# Power.net
KiCad netlist of a schematic drawn in Altium Designer
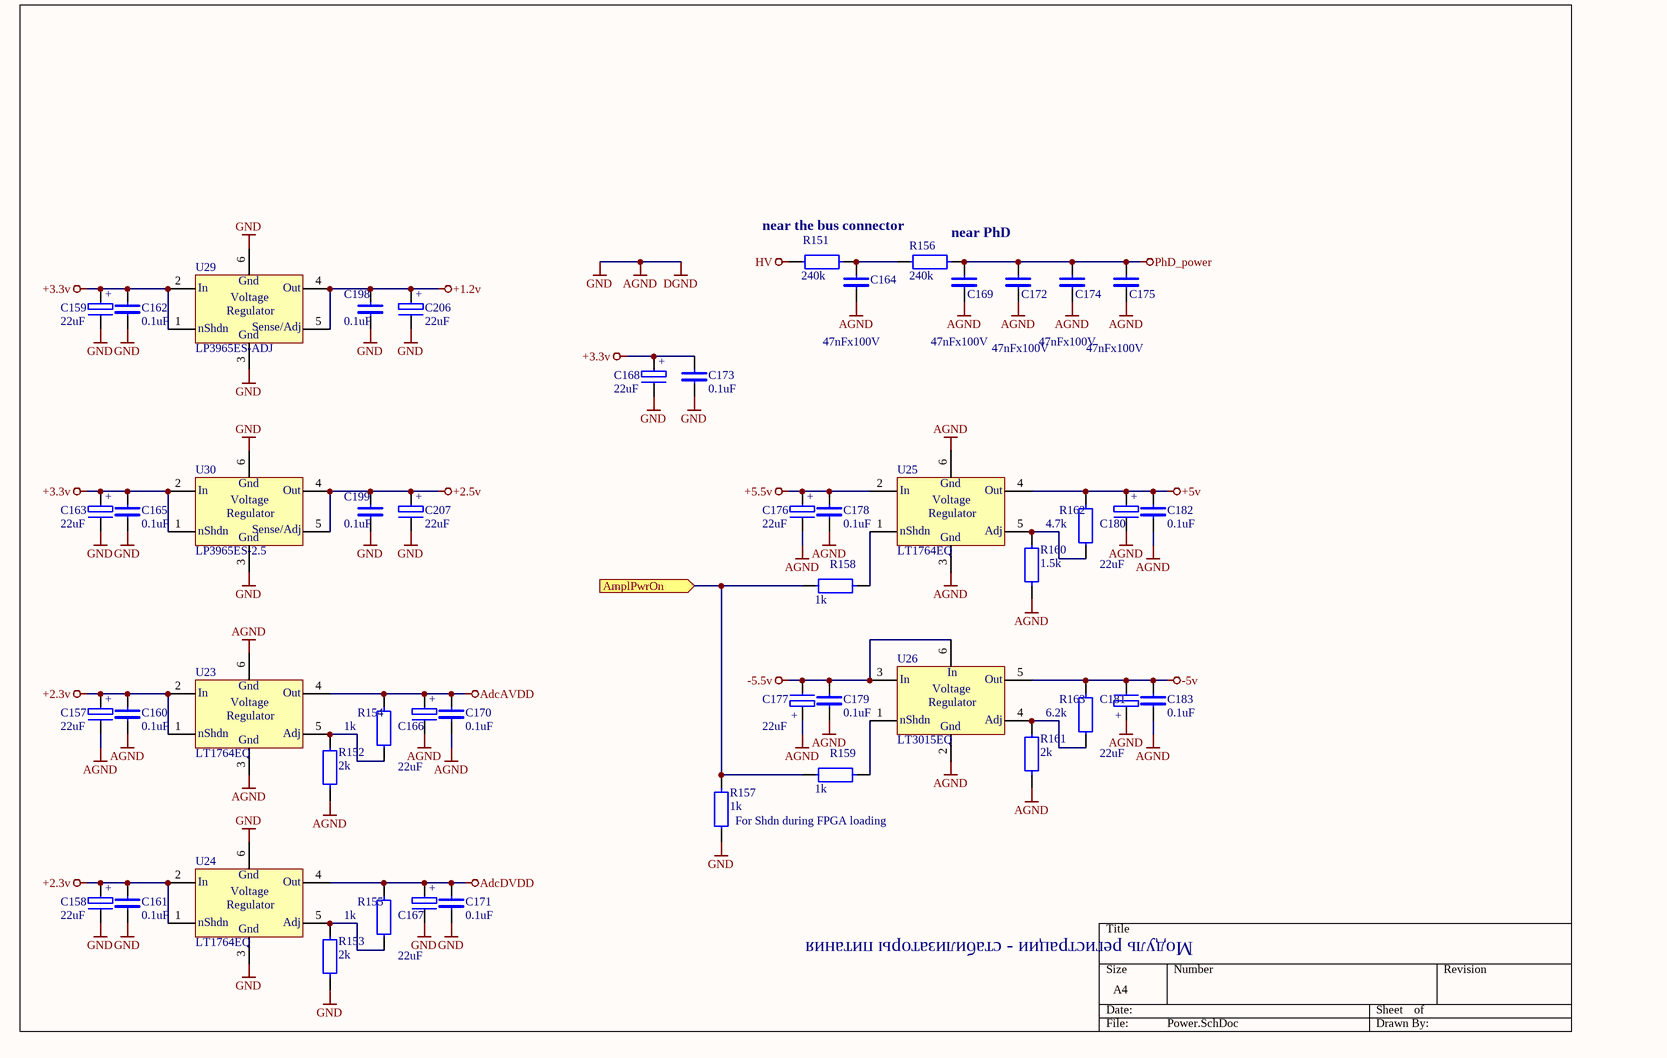
[diagram p0: Power.SchDoc]

(export (version "E")
  (design (tool "Eeschema 10.0.6"))
  (components
    (comp (ref "C157") (value "22uF") (footprint "CP6032") (libsource (lib "*") (part "C POL")))
    (comp (ref "C158") (value "22uF") (footprint "CP6032") (libsource (lib "*") (part "C POL")))
    (comp (ref "C159") (value "22uF") (footprint "CP6032") (libsource (lib "*") (part "C POL")))
    (comp (ref "C160") (value "0.1uF") (footprint "0603") (libsource (lib "*") (part "C")))
    (comp (ref "C161") (value "0.1uF") (footprint "0603") (libsource (lib "*") (part "C")))
    (comp (ref "C162") (value "0.1uF") (footprint "0603") (libsource (lib "*") (part "C")))
    (comp (ref "C163") (value "22uF") (footprint "CP6032") (libsource (lib "*") (part "C POL")))
    (comp (ref "C164") (value "47nFx100V") (footprint "1206") (libsource (lib "*") (part "C")))
    (comp (ref "C165") (value "0.1uF") (footprint "0603") (libsource (lib "*") (part "C")))
    (comp (ref "C166") (value "22uF") (footprint "CP6032") (libsource (lib "*") (part "C POL")))
    (comp (ref "C167") (value "22uF") (footprint "CP6032") (libsource (lib "*") (part "C POL")))
    (comp (ref "C168") (value "22uF") (footprint "CP6032") (libsource (lib "*") (part "C POL")))
    (comp (ref "C169") (value "47nFx100V") (footprint "1206") (libsource (lib "*") (part "C")))
    (comp (ref "C170") (value "0.1uF") (footprint "0603") (libsource (lib "*") (part "C")))
    (comp (ref "C171") (value "0.1uF") (footprint "0603") (libsource (lib "*") (part "C")))
    (comp (ref "C172") (value "47nFx100V") (footprint "1206") (libsource (lib "*") (part "C")))
    (comp (ref "C173") (value "0.1uF") (footprint "0603") (libsource (lib "*") (part "C")))
    (comp (ref "C174") (value "47nFx100V") (footprint "1206") (libsource (lib "*") (part "C")))
    (comp (ref "C175") (value "47nFx100V") (footprint "1206") (libsource (lib "*") (part "C")))
    (comp (ref "C176") (value "22uF") (footprint "CP6032") (libsource (lib "*") (part "C POL")))
    (comp (ref "C177") (value "22uF") (footprint "CP6032") (libsource (lib "*") (part "C POL")))
    (comp (ref "C178") (value "0.1uF") (footprint "0603") (libsource (lib "*") (part "C")))
    (comp (ref "C179") (value "0.1uF") (footprint "0603") (libsource (lib "*") (part "C")))
    (comp (ref "C180") (value "22uF") (footprint "CP6032") (libsource (lib "*") (part "C POL")))
    (comp (ref "C181") (value "22uF") (footprint "CP6032") (libsource (lib "*") (part "C POL")))
    (comp (ref "C182") (value "0.1uF") (footprint "0603") (libsource (lib "*") (part "C")))
    (comp (ref "C183") (value "0.1uF") (footprint "0603") (libsource (lib "*") (part "C")))
    (comp (ref "C198") (value "0.1uF") (footprint "0603") (libsource (lib "*") (part "C")))
    (comp (ref "C199") (value "0.1uF") (footprint "0603") (libsource (lib "*") (part "C")))
    (comp (ref "C206") (value "22uF") (footprint "CP6032") (libsource (lib "*") (part "C POL")))
    (comp (ref "C207") (value "22uF") (footprint "CP6032") (libsource (lib "*") (part "C POL")))
    (comp (ref "R151") (value "240k") (footprint "0805") (libsource (lib "*") (part "R")))
    (comp (ref "R152") (value "2k") (footprint "0603") (libsource (lib "*") (part "R")))
    (comp (ref "R153") (value "2k") (footprint "0603") (libsource (lib "*") (part "R")))
    (comp (ref "R154") (value "1k") (footprint "0603") (libsource (lib "*") (part "R")))
    (comp (ref "R155") (value "1k") (footprint "0603") (libsource (lib "*") (part "R")))
    (comp (ref "R156") (value "240k") (footprint "0805") (libsource (lib "*") (part "R")))
    (comp (ref "R157") (value "1k") (footprint "0603") (libsource (lib "*") (part "R")))
    (comp (ref "R158") (value "1k") (footprint "0603") (libsource (lib "*") (part "R")))
    (comp (ref "R159") (value "1k") (footprint "0603") (libsource (lib "*") (part "R")))
    (comp (ref "R160") (value "1.5k") (footprint "0603") (libsource (lib "*") (part "R")))
    (comp (ref "R161") (value "2k") (footprint "0603") (libsource (lib "*") (part "R")))
    (comp (ref "R162") (value "4.7k") (footprint "0805") (libsource (lib "*") (part "R")))
    (comp (ref "R163") (value "6.2k") (footprint "0805") (libsource (lib "*") (part "R")))
    (comp (ref "U23")
      (value "LT1764EQ")
      (footprint "TO-263-5")
      (description "Positive Linear Regulators with On/Off")
      (libsource (lib "Mylib") (part "LT1764"))
    )
    (comp (ref "U24")
      (value "LT1764EQ")
      (footprint "TO-263-5")
      (description "Positive Linear Regulators with On/Off")
      (libsource (lib "Mylib") (part "LT1764"))
    )
    (comp (ref "U25")
      (value "LT1764EQ")
      (footprint "TO-263-5")
      (description "Positive Linear Regulators with On/Off")
      (libsource (lib "Mylib") (part "LT1764"))
    )
    (comp (ref "U26")
      (value "LT3015EQ")
      (footprint "TO-263-5")
      (description "Negative Linear Regulators with On/Off")
      (libsource (lib "Mylib") (part "LT3015"))
    )
    (comp (ref "U29")
      (value "LP3965ES-ADJ")
      (footprint "TO-263-5")
      (description "Positive Linear Regulators with On/Off")
      (libsource (lib "Mylib") (part "LP3965"))
    )
    (comp (ref "U30")
      (value "LP3965ES-2.5")
      (footprint "TO-263-5")
      (description "Positive Linear Regulators with On/Off")
      (libsource (lib "Mylib") (part "LP3965"))
    )
  )
  (nets
    (net (code "1") (name "+1.2v") (class "Default")
      (node (ref "C198") (pin "2") (pinfunction "2_2") (pintype "passive"))
      (node (ref "C206") (pin "+") (pinfunction "+_+") (pintype "passive"))
      (node (ref "U29") (pin "4") (pinfunction "Out_4") (pintype "passive"))
      (node (ref "U29") (pin "5") (pinfunction "SENSE/ADJ_5") (pintype "passive"))
    )
    (net (code "2") (name "+2.3v") (class "Default")
      (node (ref "C157") (pin "+") (pinfunction "+_+") (pintype "passive"))
      (node (ref "C158") (pin "+") (pinfunction "+_+") (pintype "passive"))
      (node (ref "C160") (pin "2") (pinfunction "2_2") (pintype "passive"))
      (node (ref "C161") (pin "2") (pinfunction "2_2") (pintype "passive"))
      (node (ref "U23") (pin "1") (pinfunction "nSHDN_1") (pintype "passive"))
      (node (ref "U23") (pin "2") (pinfunction "In_2") (pintype "passive"))
      (node (ref "U24") (pin "1") (pinfunction "nSHDN_1") (pintype "passive"))
      (node (ref "U24") (pin "2") (pinfunction "In_2") (pintype "passive"))
    )
    (net (code "3") (name "+2.5v") (class "Default")
      (node (ref "C199") (pin "2") (pinfunction "2_2") (pintype "passive"))
      (node (ref "C207") (pin "+") (pinfunction "+_+") (pintype "passive"))
      (node (ref "U30") (pin "4") (pinfunction "Out_4") (pintype "passive"))
      (node (ref "U30") (pin "5") (pinfunction "SENSE/ADJ_5") (pintype "passive"))
    )
    (net (code "4") (name "+3.3v") (class "Default")
      (node (ref "C159") (pin "+") (pinfunction "+_+") (pintype "passive"))
      (node (ref "C162") (pin "2") (pinfunction "2_2") (pintype "passive"))
      (node (ref "C163") (pin "+") (pinfunction "+_+") (pintype "passive"))
      (node (ref "C165") (pin "2") (pinfunction "2_2") (pintype "passive"))
      (node (ref "C168") (pin "+") (pinfunction "+_+") (pintype "passive"))
      (node (ref "C173") (pin "2") (pinfunction "2_2") (pintype "passive"))
      (node (ref "U29") (pin "1") (pinfunction "nSHDN_1") (pintype "passive"))
      (node (ref "U29") (pin "2") (pinfunction "In_2") (pintype "passive"))
      (node (ref "U30") (pin "1") (pinfunction "nSHDN_1") (pintype "passive"))
      (node (ref "U30") (pin "2") (pinfunction "In_2") (pintype "passive"))
    )
    (net (code "5") (name "+5.5v") (class "Default")
      (node (ref "C176") (pin "+") (pinfunction "+_+") (pintype "passive"))
      (node (ref "C178") (pin "2") (pinfunction "2_2") (pintype "passive"))
      (node (ref "U25") (pin "2") (pinfunction "In_2") (pintype "passive"))
    )
    (net (code "6") (name "+5v") (class "Default")
      (node (ref "C180") (pin "+") (pinfunction "+_+") (pintype "passive"))
      (node (ref "C182") (pin "2") (pinfunction "2_2") (pintype "passive"))
      (node (ref "R162") (pin "2") (pinfunction "2_2") (pintype "passive"))
      (node (ref "U25") (pin "4") (pinfunction "Out_4") (pintype "passive"))
    )
    (net (code "7") (name "-5.5v") (class "Default")
      (node (ref "C177") (pin "-") (pinfunction "-_-") (pintype "passive"))
      (node (ref "C179") (pin "2") (pinfunction "2_2") (pintype "passive"))
      (node (ref "U26") (pin "3") (pinfunction "In_3") (pintype "passive"))
      (node (ref "U26") (pin "6") (pinfunction "Substrate_6") (pintype "passive"))
    )
    (net (code "8") (name "-5v") (class "Default")
      (node (ref "C181") (pin "-") (pinfunction "-_-") (pintype "passive"))
      (node (ref "C183") (pin "2") (pinfunction "2_2") (pintype "passive"))
      (node (ref "R163") (pin "2") (pinfunction "2_2") (pintype "passive"))
      (node (ref "U26") (pin "5") (pinfunction "Out_5") (pintype "passive"))
    )
    (net (code "9") (name "/AmplPwrOn") (class "Default")
      (node (ref "R157") (pin "2") (pinfunction "2_2") (pintype "passive"))
      (node (ref "R158") (pin "1") (pinfunction "1_1") (pintype "passive"))
      (node (ref "R159") (pin "1") (pinfunction "1_1") (pintype "passive"))
    )
    (net (code "10") (name "AGND") (class "Default")
      (node (ref "C157") (pin "-") (pinfunction "-_-") (pintype "passive"))
      (node (ref "C158") (pin "-") (pinfunction "-_-") (pintype "passive"))
      (node (ref "C159") (pin "-") (pinfunction "-_-") (pintype "passive"))
      (node (ref "C160") (pin "1") (pinfunction "1_1") (pintype "passive"))
      (node (ref "C161") (pin "1") (pinfunction "1_1") (pintype "passive"))
      (node (ref "C162") (pin "1") (pinfunction "1_1") (pintype "passive"))
      (node (ref "C163") (pin "-") (pinfunction "-_-") (pintype "passive"))
      (node (ref "C164") (pin "1") (pinfunction "1_1") (pintype "passive"))
      (node (ref "C165") (pin "1") (pinfunction "1_1") (pintype "passive"))
      (node (ref "C166") (pin "-") (pinfunction "-_-") (pintype "passive"))
      (node (ref "C167") (pin "-") (pinfunction "-_-") (pintype "passive"))
      (node (ref "C168") (pin "-") (pinfunction "-_-") (pintype "passive"))
      (node (ref "C169") (pin "1") (pinfunction "1_1") (pintype "passive"))
      (node (ref "C170") (pin "1") (pinfunction "1_1") (pintype "passive"))
      (node (ref "C171") (pin "1") (pinfunction "1_1") (pintype "passive"))
      (node (ref "C172") (pin "1") (pinfunction "1_1") (pintype "passive"))
      (node (ref "C173") (pin "1") (pinfunction "1_1") (pintype "passive"))
      (node (ref "C174") (pin "1") (pinfunction "1_1") (pintype "passive"))
      (node (ref "C175") (pin "1") (pinfunction "1_1") (pintype "passive"))
      (node (ref "C176") (pin "-") (pinfunction "-_-") (pintype "passive"))
      (node (ref "C177") (pin "+") (pinfunction "+_+") (pintype "passive"))
      (node (ref "C178") (pin "1") (pinfunction "1_1") (pintype "passive"))
      (node (ref "C179") (pin "1") (pinfunction "1_1") (pintype "passive"))
      (node (ref "C180") (pin "-") (pinfunction "-_-") (pintype "passive"))
      (node (ref "C181") (pin "+") (pinfunction "+_+") (pintype "passive"))
      (node (ref "C182") (pin "1") (pinfunction "1_1") (pintype "passive"))
      (node (ref "C183") (pin "1") (pinfunction "1_1") (pintype "passive"))
      (node (ref "C198") (pin "1") (pinfunction "1_1") (pintype "passive"))
      (node (ref "C199") (pin "1") (pinfunction "1_1") (pintype "passive"))
      (node (ref "C206") (pin "-") (pinfunction "-_-") (pintype "passive"))
      (node (ref "C207") (pin "-") (pinfunction "-_-") (pintype "passive"))
      (node (ref "R152") (pin "2") (pinfunction "2_2") (pintype "passive"))
      (node (ref "R153") (pin "2") (pinfunction "2_2") (pintype "passive"))
      (node (ref "R157") (pin "1") (pinfunction "1_1") (pintype "passive"))
      (node (ref "R160") (pin "2") (pinfunction "2_2") (pintype "passive"))
      (node (ref "R161") (pin "2") (pinfunction "2_2") (pintype "passive"))
      (node (ref "U23") (pin "3") (pinfunction "GND_3") (pintype "passive"))
      (node (ref "U23") (pin "6") (pinfunction "Substrate_6") (pintype "passive"))
      (node (ref "U24") (pin "3") (pinfunction "GND_3") (pintype "passive"))
      (node (ref "U24") (pin "6") (pinfunction "Substrate_6") (pintype "passive"))
      (node (ref "U25") (pin "3") (pinfunction "GND_3") (pintype "passive"))
      (node (ref "U25") (pin "6") (pinfunction "Substrate_6") (pintype "passive"))
      (node (ref "U26") (pin "2") (pinfunction "GND_2") (pintype "passive"))
      (node (ref "U29") (pin "3") (pinfunction "GND_3") (pintype "passive"))
      (node (ref "U29") (pin "6") (pinfunction "Substrate_6") (pintype "passive"))
      (node (ref "U30") (pin "3") (pinfunction "GND_3") (pintype "passive"))
      (node (ref "U30") (pin "6") (pinfunction "Substrate_6") (pintype "passive"))
    )
    (net (code "11") (name "AdcAVDD") (class "Default")
      (node (ref "C166") (pin "+") (pinfunction "+_+") (pintype "passive"))
      (node (ref "C170") (pin "2") (pinfunction "2_2") (pintype "passive"))
      (node (ref "R154") (pin "2") (pinfunction "2_2") (pintype "passive"))
      (node (ref "U23") (pin "4") (pinfunction "Out_4") (pintype "passive"))
    )
    (net (code "12") (name "AdcDVDD") (class "Default")
      (node (ref "C167") (pin "+") (pinfunction "+_+") (pintype "passive"))
      (node (ref "C171") (pin "2") (pinfunction "2_2") (pintype "passive"))
      (node (ref "R155") (pin "2") (pinfunction "2_2") (pintype "passive"))
      (node (ref "U24") (pin "4") (pinfunction "Out_4") (pintype "passive"))
    )
    (net (code "13") (name "HV") (class "Default")
      (node (ref "R151") (pin "1") (pinfunction "1_1") (pintype "passive"))
    )
    (net (code "14") (name "Net-(C164-Pad2)") (class "Default")
      (node (ref "C164") (pin "2") (pinfunction "2_2") (pintype "passive"))
      (node (ref "R151") (pin "2") (pinfunction "2_2") (pintype "passive"))
      (node (ref "R156") (pin "1") (pinfunction "1_1") (pintype "passive"))
    )
    (net (code "15") (name "Net-(U23-SENSE{slash}ADJ)") (class "Default")
      (node (ref "R152") (pin "1") (pinfunction "1_1") (pintype "passive"))
      (node (ref "R154") (pin "1") (pinfunction "1_1") (pintype "passive"))
      (node (ref "U23") (pin "5") (pinfunction "SENSE/ADJ_5") (pintype "passive"))
    )
    (net (code "16") (name "Net-(U24-SENSE{slash}ADJ)") (class "Default")
      (node (ref "R153") (pin "1") (pinfunction "1_1") (pintype "passive"))
      (node (ref "R155") (pin "1") (pinfunction "1_1") (pintype "passive"))
      (node (ref "U24") (pin "5") (pinfunction "SENSE/ADJ_5") (pintype "passive"))
    )
    (net (code "17") (name "Net-(U25-SENSE{slash}ADJ)") (class "Default")
      (node (ref "R160") (pin "1") (pinfunction "1_1") (pintype "passive"))
      (node (ref "R162") (pin "1") (pinfunction "1_1") (pintype "passive"))
      (node (ref "U25") (pin "5") (pinfunction "SENSE/ADJ_5") (pintype "passive"))
    )
    (net (code "18") (name "Net-(U25-nSHDN)") (class "Default")
      (node (ref "R158") (pin "2") (pinfunction "2_2") (pintype "passive"))
      (node (ref "U25") (pin "1") (pinfunction "nSHDN_1") (pintype "passive"))
    )
    (net (code "19") (name "Net-(U26-SENSE{slash}ADJ)") (class "Default")
      (node (ref "R161") (pin "1") (pinfunction "1_1") (pintype "passive"))
      (node (ref "R163") (pin "1") (pinfunction "1_1") (pintype "passive"))
      (node (ref "U26") (pin "4") (pinfunction "SENSE/ADJ_4") (pintype "passive"))
    )
    (net (code "20") (name "Net-(U26-nSHDN)") (class "Default")
      (node (ref "R159") (pin "2") (pinfunction "2_2") (pintype "passive"))
      (node (ref "U26") (pin "1") (pinfunction "nSHDN_1") (pintype "passive"))
    )
    (net (code "21") (name "PhD_power") (class "Default")
      (node (ref "C169") (pin "2") (pinfunction "2_2") (pintype "passive"))
      (node (ref "C172") (pin "2") (pinfunction "2_2") (pintype "passive"))
      (node (ref "C174") (pin "2") (pinfunction "2_2") (pintype "passive"))
      (node (ref "C175") (pin "2") (pinfunction "2_2") (pintype "passive"))
      (node (ref "R156") (pin "2") (pinfunction "2_2") (pintype "passive"))
    )
  )
)
